# Sequencer_RevB.net
KiCad netlist of a schematic drawn in EAGLE
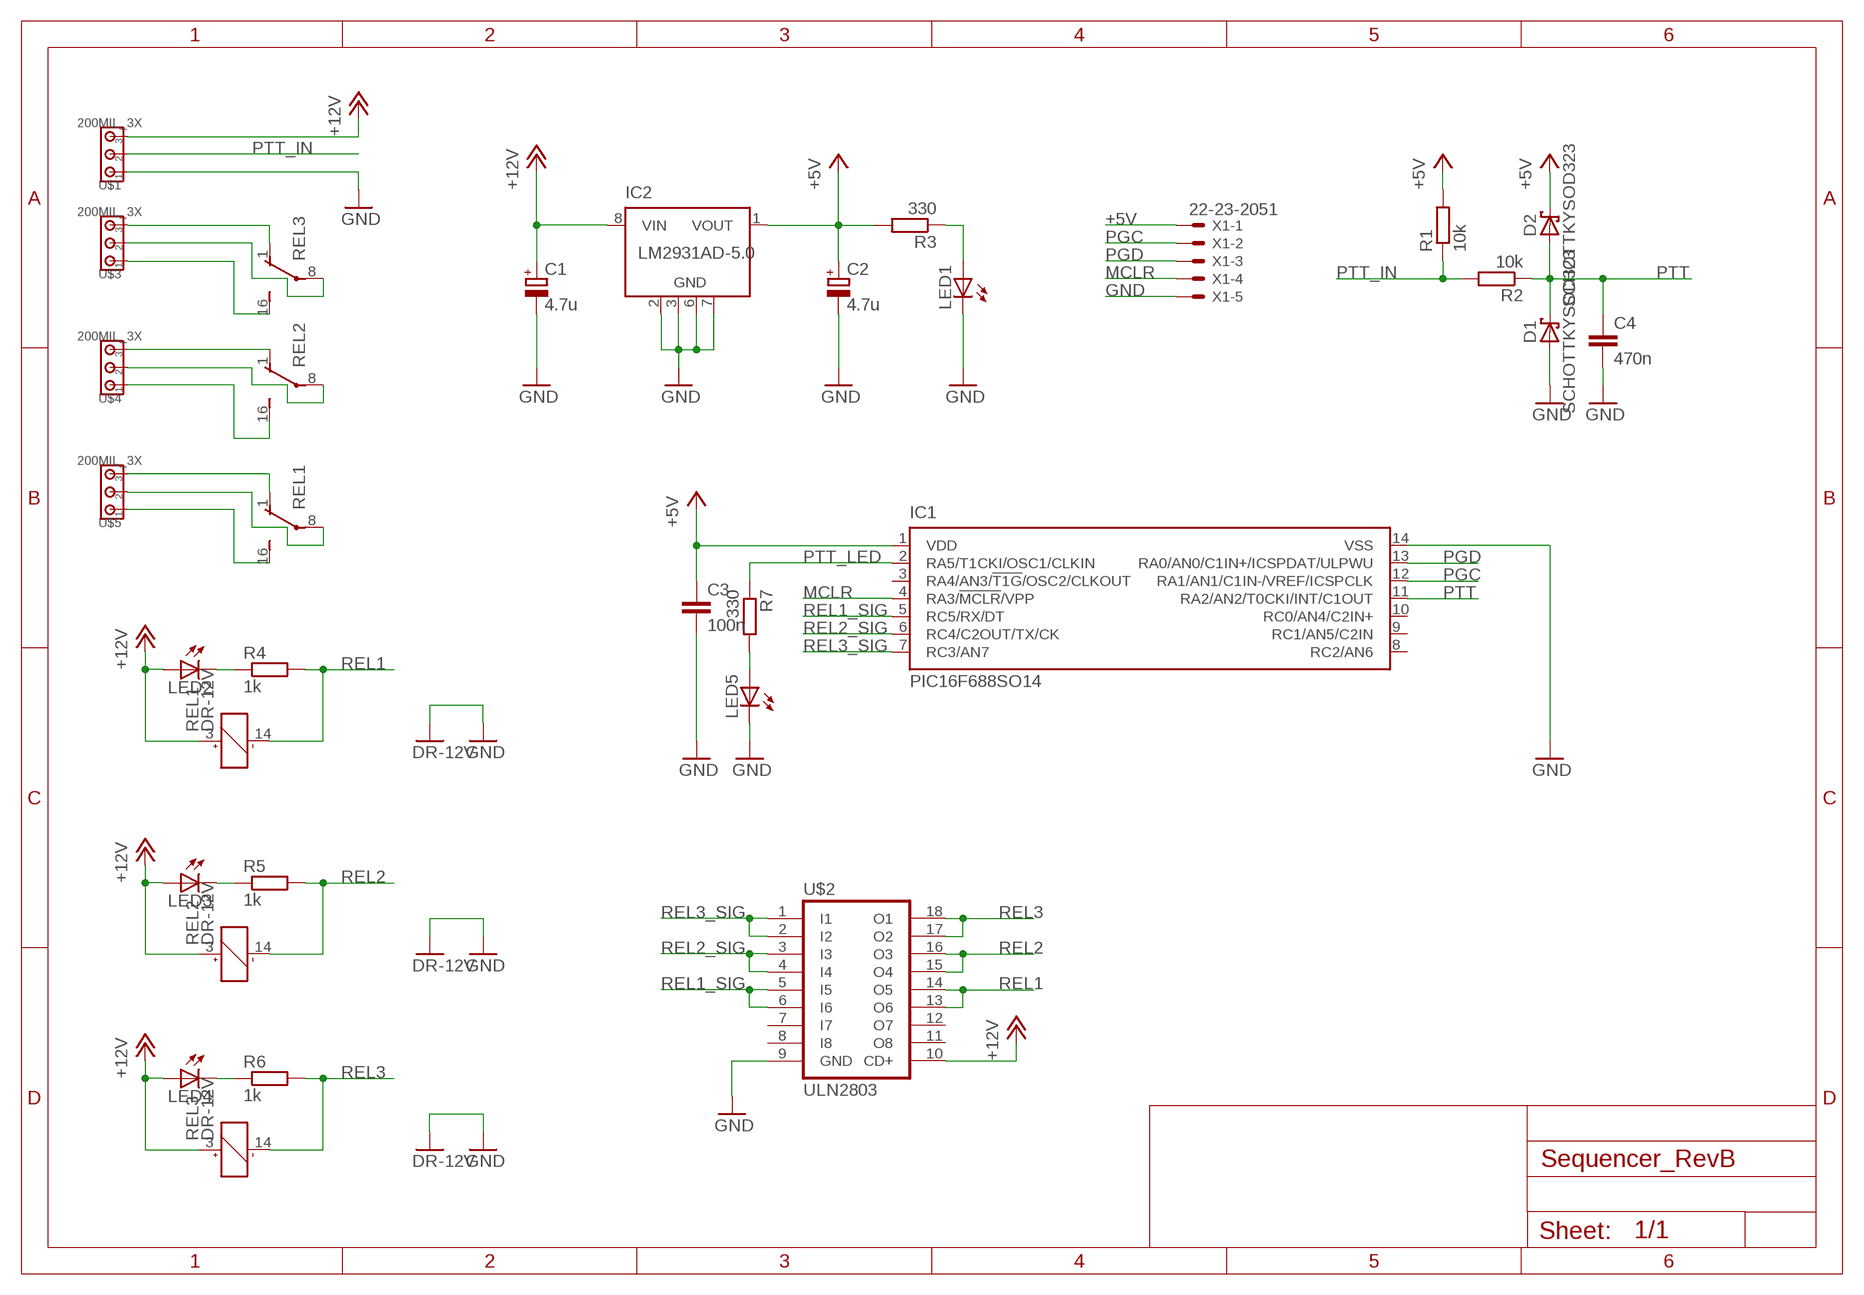
[diagram p0: schematic, sheet 1]

(export (version "E")
  (design (tool "Eeschema 10.0.6"))
  (components
    (comp (ref "C1")
      (value "4.7u")
      (footprint "eagle-import:SMC_C")
      (libsource (lib "eagle-import") (part "C_POLARIZEDSMC_C"))
    )
    (comp (ref "C2")
      (value "4.7u")
      (footprint "eagle-import:SMC_C")
      (libsource (lib "eagle-import") (part "C_POLARIZEDSMC_C"))
    )
    (comp (ref "C3")
      (value "100n")
      (footprint "eagle-import:C0805")
      (libsource (lib "eagle-import") (part "CC0805"))
    )
    (comp (ref "C4")
      (value "470n")
      (footprint "eagle-import:C0805")
      (libsource (lib "eagle-import") (part "CC0805"))
    )
    (comp (ref "D1")
      (value "SCHOTTKYSOD323")
      (footprint "eagle-import:SOD323")
      (libsource (lib "eagle-import") (part "SCHOTTKYSOD323"))
    )
    (comp (ref "D2")
      (value "SCHOTTKYSOD323")
      (footprint "eagle-import:SOD323")
      (libsource (lib "eagle-import") (part "SCHOTTKYSOD323"))
    )
    (comp (ref "IC1")
      (value "PIC16F688SO14")
      (footprint "eagle-import:SO14")
      (libsource (lib "eagle-import") (part "PIC16F688SO14"))
    )
    (comp (ref "IC2")
      (value "LM2931AD-5.0")
      (footprint "eagle-import:SO8")
      (libsource (lib "eagle-import") (part "LM2931AD-5.0"))
    )
    (comp (ref "LED1")
      (value "LED0805")
      (footprint "eagle-import:LED0805")
      (libsource (lib "eagle-import") (part "LED0805"))
    )
    (comp (ref "LED2")
      (value "LED0805")
      (footprint "eagle-import:LED0805")
      (libsource (lib "eagle-import") (part "LED0805"))
    )
    (comp (ref "LED3")
      (value "LED0805")
      (footprint "eagle-import:LED0805")
      (libsource (lib "eagle-import") (part "LED0805"))
    )
    (comp (ref "LED4")
      (value "LED0805")
      (footprint "eagle-import:LED0805")
      (libsource (lib "eagle-import") (part "LED0805"))
    )
    (comp (ref "LED5")
      (value "LED0805")
      (footprint "eagle-import:LED0805")
      (libsource (lib "eagle-import") (part "LED0805"))
    )
    (comp (ref "R1")
      (value "10k")
      (footprint "eagle-import:R0805")
      (libsource (lib "eagle-import") (part "RESISTORR0805"))
    )
    (comp (ref "R2")
      (value "10k")
      (footprint "eagle-import:R0805")
      (libsource (lib "eagle-import") (part "RESISTORR0805"))
    )
    (comp (ref "R3")
      (value "330")
      (footprint "eagle-import:R0805")
      (libsource (lib "eagle-import") (part "RESISTORR0805"))
    )
    (comp (ref "R4")
      (value "1k")
      (footprint "eagle-import:R0805")
      (libsource (lib "eagle-import") (part "RESISTORR0805"))
    )
    (comp (ref "R5")
      (value "1k")
      (footprint "eagle-import:R0805")
      (libsource (lib "eagle-import") (part "RESISTORR0805"))
    )
    (comp (ref "R6")
      (value "1k")
      (footprint "eagle-import:R0805")
      (libsource (lib "eagle-import") (part "RESISTORR0805"))
    )
    (comp (ref "R7")
      (value "330")
      (footprint "eagle-import:R0805")
      (libsource (lib "eagle-import") (part "RESISTORR0805"))
    )
    (comp (ref "REL1")
      (value "DR-12V")
      (footprint "eagle-import:DR-12V")
      (libsource (lib "eagle-import") (part "DR-12V"))
    )
    (comp (ref "REL2")
      (value "DR-12V")
      (footprint "eagle-import:DR-12V")
      (libsource (lib "eagle-import") (part "DR-12V"))
    )
    (comp (ref "REL3")
      (value "DR-12V")
      (footprint "eagle-import:DR-12V")
      (libsource (lib "eagle-import") (part "DR-12V"))
    )
    (comp (ref "U$1")
      (value "200MIL_3X")
      (footprint "eagle-import:200MIL_3X")
      (libsource (lib "eagle-import") (part "200MIL_3X"))
    )
    (comp (ref "U$2")
      (value "ULN2803")
      (footprint "eagle-import:SO18W")
      (libsource (lib "eagle-import") (part "ULN2803"))
    )
    (comp (ref "U$3")
      (value "200MIL_3X")
      (footprint "eagle-import:200MIL_3X")
      (libsource (lib "eagle-import") (part "200MIL_3X"))
    )
    (comp (ref "U$4")
      (value "200MIL_3X")
      (footprint "eagle-import:200MIL_3X")
      (libsource (lib "eagle-import") (part "200MIL_3X"))
    )
    (comp (ref "U$5")
      (value "200MIL_3X")
      (footprint "eagle-import:200MIL_3X")
      (libsource (lib "eagle-import") (part "200MIL_3X"))
    )
    (comp (ref "X1")
      (value "22-23-2051")
      (footprint "eagle-import:22-23-2051")
      (fields (field (name "MF") "MOLEX"))
      (libsource (lib "eagle-import") (part "22-23-2051"))
    )
  )
  (nets
    (net (code "1") (name "+5V") (class "Default")
      (node (ref "C2") (pin "+") (pinfunction "+_+") (pintype "passive"))
      (node (ref "C3") (pin "1") (pinfunction "1_1") (pintype "passive"))
      (node (ref "D2") (pin "C") (pinfunction "C_C") (pintype "passive"))
      (node (ref "IC1") (pin "1") (pinfunction "VDD_1") (pintype "power_in"))
      (node (ref "IC2") (pin "1") (pinfunction "VOUT_1") (pintype "output"))
      (node (ref "R1") (pin "2") (pinfunction "2_2") (pintype "passive"))
      (node (ref "R3") (pin "2") (pinfunction "2_2") (pintype "passive"))
      (node (ref "X1") (pin "1") (pinfunction "S_1") (pintype "passive"))
    )
    (net (code "2") (name "+12V") (class "Default")
      (node (ref "C1") (pin "+") (pinfunction "+_+") (pintype "passive"))
      (node (ref "IC2") (pin "8") (pinfunction "VIN_8") (pintype "passive"))
      (node (ref "LED2") (pin "A") (pinfunction "A_A") (pintype "passive"))
      (node (ref "LED3") (pin "A") (pinfunction "A_A") (pintype "passive"))
      (node (ref "LED4") (pin "A") (pinfunction "A_A") (pintype "passive"))
      (node (ref "REL1") (pin "3") (pinfunction "+_3") (pintype "passive"))
      (node (ref "REL2") (pin "3") (pinfunction "+_3") (pintype "passive"))
      (node (ref "REL3") (pin "3") (pinfunction "+_3") (pintype "passive"))
      (node (ref "U$1") (pin "3") (pinfunction "3_3") (pintype "passive"))
      (node (ref "U$2") (pin "10") (pinfunction "CD+_10") (pintype "passive"))
    )
    (net (code "3") (name "/MCLR") (class "Default")
      (node (ref "IC1") (pin "4") (pinfunction "RA3/~{MCLR}/VPP_4") (pintype "bidirectional"))
      (node (ref "X1") (pin "4") (pinfunction "S_4") (pintype "passive"))
    )
    (net (code "4") (name "/PGC") (class "Default")
      (node (ref "IC1") (pin "12") (pinfunction "RA1/AN1/C1IN-/VREF/ICSPCLK_12") (pintype "bidirectional"))
      (node (ref "X1") (pin "2") (pinfunction "S_2") (pintype "passive"))
    )
    (net (code "5") (name "/PGD") (class "Default")
      (node (ref "IC1") (pin "13") (pinfunction "RA0/AN0/C1IN+/ICSPDAT/ULPWU_13") (pintype "bidirectional"))
      (node (ref "X1") (pin "3") (pinfunction "S_3") (pintype "passive"))
    )
    (net (code "6") (name "/PTT") (class "Default")
      (node (ref "C4") (pin "1") (pinfunction "1_1") (pintype "passive"))
      (node (ref "D1") (pin "C") (pinfunction "C_C") (pintype "passive"))
      (node (ref "D2") (pin "A") (pinfunction "A_A") (pintype "passive"))
      (node (ref "IC1") (pin "11") (pinfunction "RA2/AN2/T0CKI/INT/C1OUT_11") (pintype "bidirectional"))
      (node (ref "R2") (pin "1") (pinfunction "1_1") (pintype "passive"))
    )
    (net (code "7") (name "/PTT_IN") (class "Default")
      (node (ref "R1") (pin "1") (pinfunction "1_1") (pintype "passive"))
      (node (ref "R2") (pin "2") (pinfunction "2_2") (pintype "passive"))
      (node (ref "U$1") (pin "2") (pinfunction "2_2") (pintype "passive"))
    )
    (net (code "8") (name "/PTT_LED") (class "Default")
      (node (ref "IC1") (pin "2") (pinfunction "RA5/T1CKI/OSC1/CLKIN_2") (pintype "input"))
      (node (ref "R7") (pin "1") (pinfunction "1_1") (pintype "passive"))
    )
    (net (code "9") (name "/REL1") (class "Default")
      (node (ref "R4") (pin "2") (pinfunction "2_2") (pintype "passive"))
      (node (ref "REL1") (pin "14") (pinfunction "-_14") (pintype "passive"))
      (node (ref "U$2") (pin "13") (pinfunction "O6_13") (pintype "open_collector"))
      (node (ref "U$2") (pin "14") (pinfunction "O5_14") (pintype "open_collector"))
    )
    (net (code "10") (name "/REL1_SIG") (class "Default")
      (node (ref "IC1") (pin "5") (pinfunction "RC5/RX/DT_5") (pintype "bidirectional"))
      (node (ref "U$2") (pin "5") (pinfunction "I5_5") (pintype "input"))
      (node (ref "U$2") (pin "6") (pinfunction "I6_6") (pintype "input"))
    )
    (net (code "11") (name "/REL2") (class "Default")
      (node (ref "R5") (pin "2") (pinfunction "2_2") (pintype "passive"))
      (node (ref "REL2") (pin "14") (pinfunction "-_14") (pintype "passive"))
      (node (ref "U$2") (pin "15") (pinfunction "O4_15") (pintype "open_collector"))
      (node (ref "U$2") (pin "16") (pinfunction "O3_16") (pintype "open_collector"))
    )
    (net (code "12") (name "/REL2_SIG") (class "Default")
      (node (ref "IC1") (pin "6") (pinfunction "RC4/C2OUT/TX/CK_6") (pintype "bidirectional"))
      (node (ref "U$2") (pin "3") (pinfunction "I3_3") (pintype "input"))
      (node (ref "U$2") (pin "4") (pinfunction "I4_4") (pintype "input"))
    )
    (net (code "13") (name "/REL3") (class "Default")
      (node (ref "R6") (pin "2") (pinfunction "2_2") (pintype "passive"))
      (node (ref "REL3") (pin "14") (pinfunction "-_14") (pintype "passive"))
      (node (ref "U$2") (pin "17") (pinfunction "O2_17") (pintype "open_collector"))
      (node (ref "U$2") (pin "18") (pinfunction "O1_18") (pintype "open_collector"))
    )
    (net (code "14") (name "/REL3_SIG") (class "Default")
      (node (ref "IC1") (pin "7") (pinfunction "RC3/AN7_7") (pintype "bidirectional"))
      (node (ref "U$2") (pin "1") (pinfunction "I1_1") (pintype "input"))
      (node (ref "U$2") (pin "2") (pinfunction "I2_2") (pintype "input"))
    )
    (net (code "15") (name "GND") (class "Default")
      (node (ref "C1") (pin "-") (pinfunction "-_-") (pintype "passive"))
      (node (ref "C2") (pin "-") (pinfunction "-_-") (pintype "passive"))
      (node (ref "C3") (pin "2") (pinfunction "2_2") (pintype "passive"))
      (node (ref "C4") (pin "2") (pinfunction "2_2") (pintype "passive"))
      (node (ref "D1") (pin "A") (pinfunction "A_A") (pintype "passive"))
      (node (ref "IC1") (pin "14") (pinfunction "VSS_14") (pintype "power_in"))
      (node (ref "IC2") (pin "2") (pinfunction "GND_2") (pintype "power_in"))
      (node (ref "IC2") (pin "3") (pinfunction "GND_3") (pintype "power_in"))
      (node (ref "IC2") (pin "6") (pinfunction "GND_6") (pintype "power_in"))
      (node (ref "IC2") (pin "7") (pinfunction "GND_7") (pintype "power_in"))
      (node (ref "LED1") (pin "C") (pinfunction "C_C") (pintype "passive"))
      (node (ref "LED5") (pin "C") (pinfunction "C_C") (pintype "passive"))
      (node (ref "REL1") (pin "9") (pinfunction "GND_9") (pintype "power_in"))
      (node (ref "REL2") (pin "9") (pinfunction "GND_9") (pintype "power_in"))
      (node (ref "REL3") (pin "9") (pinfunction "GND_9") (pintype "power_in"))
      (node (ref "U$1") (pin "1") (pinfunction "1_1") (pintype "passive"))
      (node (ref "U$2") (pin "9") (pinfunction "GND_9") (pintype "power_in"))
      (node (ref "X1") (pin "5") (pinfunction "S_5") (pintype "passive"))
    )
    (net (code "16") (name "Net-(LED1-PadA)") (class "Default")
      (node (ref "LED1") (pin "A") (pinfunction "A_A") (pintype "passive"))
      (node (ref "R3") (pin "1") (pinfunction "1_1") (pintype "passive"))
    )
    (net (code "17") (name "Net-(LED2-PadC)") (class "Default")
      (node (ref "LED2") (pin "C") (pinfunction "C_C") (pintype "passive"))
      (node (ref "R4") (pin "1") (pinfunction "1_1") (pintype "passive"))
    )
    (net (code "18") (name "Net-(LED3-PadC)") (class "Default")
      (node (ref "LED3") (pin "C") (pinfunction "C_C") (pintype "passive"))
      (node (ref "R5") (pin "1") (pinfunction "1_1") (pintype "passive"))
    )
    (net (code "19") (name "Net-(LED4-PadC)") (class "Default")
      (node (ref "LED4") (pin "C") (pinfunction "C_C") (pintype "passive"))
      (node (ref "R6") (pin "1") (pinfunction "1_1") (pintype "passive"))
    )
    (net (code "20") (name "Net-(LED5-PadA)") (class "Default")
      (node (ref "LED5") (pin "A") (pinfunction "A_A") (pintype "passive"))
      (node (ref "R7") (pin "2") (pinfunction "2_2") (pintype "passive"))
    )
    (net (code "21") (name "Net-(REL1B-O)") (class "Default")
      (node (ref "REL1") (pin "1") (pinfunction "O_1") (pintype "passive"))
      (node (ref "U$5") (pin "3") (pinfunction "3_3") (pintype "passive"))
    )
    (net (code "22") (name "Net-(REL1B-P)") (class "Default")
      (node (ref "REL1") (pin "8") (pinfunction "P_8") (pintype "passive"))
      (node (ref "U$5") (pin "2") (pinfunction "2_2") (pintype "passive"))
    )
    (net (code "23") (name "Net-(REL1B-S)") (class "Default")
      (node (ref "REL1") (pin "16") (pinfunction "S_16") (pintype "passive"))
      (node (ref "U$5") (pin "1") (pinfunction "1_1") (pintype "passive"))
    )
    (net (code "24") (name "Net-(REL2B-O)") (class "Default")
      (node (ref "REL2") (pin "1") (pinfunction "O_1") (pintype "passive"))
      (node (ref "U$4") (pin "3") (pinfunction "3_3") (pintype "passive"))
    )
    (net (code "25") (name "Net-(REL2B-P)") (class "Default")
      (node (ref "REL2") (pin "8") (pinfunction "P_8") (pintype "passive"))
      (node (ref "U$4") (pin "2") (pinfunction "2_2") (pintype "passive"))
    )
    (net (code "26") (name "Net-(REL2B-S)") (class "Default")
      (node (ref "REL2") (pin "16") (pinfunction "S_16") (pintype "passive"))
      (node (ref "U$4") (pin "1") (pinfunction "1_1") (pintype "passive"))
    )
    (net (code "27") (name "Net-(REL3B-O)") (class "Default")
      (node (ref "REL3") (pin "1") (pinfunction "O_1") (pintype "passive"))
      (node (ref "U$3") (pin "3") (pinfunction "3_3") (pintype "passive"))
    )
    (net (code "28") (name "Net-(REL3B-P)") (class "Default")
      (node (ref "REL3") (pin "8") (pinfunction "P_8") (pintype "passive"))
      (node (ref "U$3") (pin "2") (pinfunction "2_2") (pintype "passive"))
    )
    (net (code "29") (name "Net-(REL3B-S)") (class "Default")
      (node (ref "REL3") (pin "16") (pinfunction "S_16") (pintype "passive"))
      (node (ref "U$3") (pin "1") (pinfunction "1_1") (pintype "passive"))
    )
    (net (code "30") (name "unconnected-(IC1-RA4{slash}AN3{slash}~{T1G}{slash}OSC2{slash}CLKOUT-Pad3)") (class "Default")
      (node (ref "IC1") (pin "3") (pinfunction "RA4/AN3/~{T1G}/OSC2/CLKOUT_3") (pintype "bidirectional"))
    )
    (net (code "31") (name "unconnected-(IC1-RC0{slash}AN4{slash}C2IN+-Pad10)") (class "Default")
      (node (ref "IC1") (pin "10") (pinfunction "RC0/AN4/C2IN+_10") (pintype "bidirectional"))
    )
    (net (code "32") (name "unconnected-(IC1-RC1{slash}AN5{slash}C2IN-Pad9)") (class "Default")
      (node (ref "IC1") (pin "9") (pinfunction "RC1/AN5/C2IN_9") (pintype "bidirectional"))
    )
    (net (code "33") (name "unconnected-(IC1-RC2{slash}AN6-Pad8)") (class "Default")
      (node (ref "IC1") (pin "8") (pinfunction "RC2/AN6_8") (pintype "bidirectional"))
    )
    (net (code "34") (name "unconnected-(U$2-I7-Pad7)") (class "Default")
      (node (ref "U$2") (pin "7") (pinfunction "I7_7") (pintype "input"))
    )
    (net (code "35") (name "unconnected-(U$2-I8-Pad8)") (class "Default")
      (node (ref "U$2") (pin "8") (pinfunction "I8_8") (pintype "input"))
    )
    (net (code "36") (name "unconnected-(U$2-O7-Pad12)") (class "Default")
      (node (ref "U$2") (pin "12") (pinfunction "O7_12") (pintype "open_collector"))
    )
    (net (code "37") (name "unconnected-(U$2-O8-Pad11)") (class "Default")
      (node (ref "U$2") (pin "11") (pinfunction "O8_11") (pintype "open_collector"))
    )
  )
)
